# RingLight.net
KiCad netlist of a schematic drawn in EAGLE
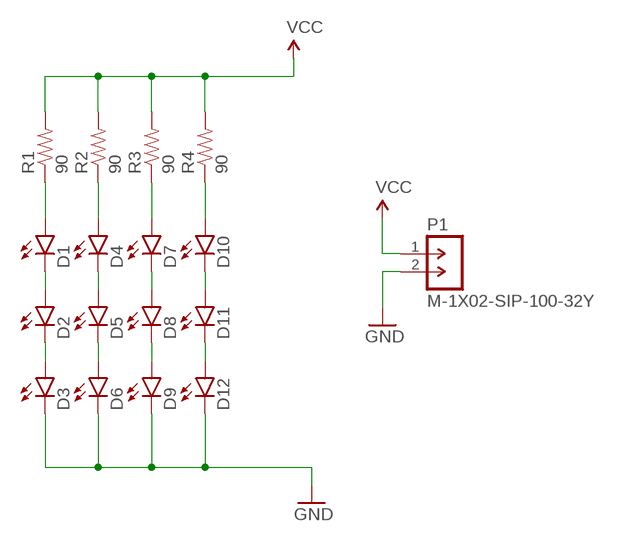
[diagram p0: schematic, sheet 1]

(export (version "E")
  (design (tool "Eeschema 10.0.6"))
  (components
    (comp (ref "D1")
      (value "LED1206")
      (footprint "eagle-import:LED-1206")
      (libsource (lib "eagle-import") (part "LED1206"))
    )
    (comp (ref "D2")
      (value "LED1206")
      (footprint "eagle-import:LED-1206")
      (libsource (lib "eagle-import") (part "LED1206"))
    )
    (comp (ref "D3")
      (value "LED1206")
      (footprint "eagle-import:LED-1206")
      (libsource (lib "eagle-import") (part "LED1206"))
    )
    (comp (ref "D4")
      (value "LED1206")
      (footprint "eagle-import:LED-1206")
      (libsource (lib "eagle-import") (part "LED1206"))
    )
    (comp (ref "D5")
      (value "LED1206")
      (footprint "eagle-import:LED-1206")
      (libsource (lib "eagle-import") (part "LED1206"))
    )
    (comp (ref "D6")
      (value "LED1206")
      (footprint "eagle-import:LED-1206")
      (libsource (lib "eagle-import") (part "LED1206"))
    )
    (comp (ref "D7")
      (value "LED1206")
      (footprint "eagle-import:LED-1206")
      (libsource (lib "eagle-import") (part "LED1206"))
    )
    (comp (ref "D8")
      (value "LED1206")
      (footprint "eagle-import:LED-1206")
      (libsource (lib "eagle-import") (part "LED1206"))
    )
    (comp (ref "D9")
      (value "LED1206")
      (footprint "eagle-import:LED-1206")
      (libsource (lib "eagle-import") (part "LED1206"))
    )
    (comp (ref "D10")
      (value "LED1206")
      (footprint "eagle-import:LED-1206")
      (libsource (lib "eagle-import") (part "LED1206"))
    )
    (comp (ref "D11")
      (value "LED1206")
      (footprint "eagle-import:LED-1206")
      (libsource (lib "eagle-import") (part "LED1206"))
    )
    (comp (ref "D12")
      (value "LED1206")
      (footprint "eagle-import:LED-1206")
      (libsource (lib "eagle-import") (part "LED1206"))
    )
    (comp (ref "P1")
      (value "M-1X02-SIP-100-32Y")
      (footprint "eagle-import:SIP-100-02-32Y")
      (libsource (lib "eagle-import") (part "M-1X02-SIP-100-32Y"))
    )
    (comp (ref "R1")
      (value "90")
      (footprint "eagle-import:1206")
      (libsource (lib "eagle-import") (part "RESISTOR1206"))
    )
    (comp (ref "R2")
      (value "90")
      (footprint "eagle-import:1206")
      (libsource (lib "eagle-import") (part "RESISTOR1206"))
    )
    (comp (ref "R3")
      (value "90")
      (footprint "eagle-import:1206")
      (libsource (lib "eagle-import") (part "RESISTOR1206"))
    )
    (comp (ref "R4")
      (value "90")
      (footprint "eagle-import:1206")
      (libsource (lib "eagle-import") (part "RESISTOR1206"))
    )
  )
  (nets
    (net (code "1") (name "GND") (class "Default")
      (node (ref "D12") (pin "C") (pinfunction "C_C") (pintype "passive"))
      (node (ref "D3") (pin "C") (pinfunction "C_C") (pintype "passive"))
      (node (ref "D6") (pin "C") (pinfunction "C_C") (pintype "passive"))
      (node (ref "D9") (pin "C") (pinfunction "C_C") (pintype "passive"))
      (node (ref "P1") (pin "2") (pinfunction "2_2") (pintype "passive"))
    )
    (net (code "2") (name "Net-(D1-PadA)") (class "Default")
      (node (ref "D1") (pin "A") (pinfunction "A_A") (pintype "passive"))
      (node (ref "R1") (pin "1") (pinfunction "1_1") (pintype "passive"))
    )
    (net (code "3") (name "Net-(D1-PadC)") (class "Default")
      (node (ref "D1") (pin "C") (pinfunction "C_C") (pintype "passive"))
      (node (ref "D2") (pin "A") (pinfunction "A_A") (pintype "passive"))
    )
    (net (code "4") (name "Net-(D2-PadC)") (class "Default")
      (node (ref "D2") (pin "C") (pinfunction "C_C") (pintype "passive"))
      (node (ref "D3") (pin "A") (pinfunction "A_A") (pintype "passive"))
    )
    (net (code "5") (name "Net-(D4-PadA)") (class "Default")
      (node (ref "D4") (pin "A") (pinfunction "A_A") (pintype "passive"))
      (node (ref "R2") (pin "1") (pinfunction "1_1") (pintype "passive"))
    )
    (net (code "6") (name "Net-(D4-PadC)") (class "Default")
      (node (ref "D4") (pin "C") (pinfunction "C_C") (pintype "passive"))
      (node (ref "D5") (pin "A") (pinfunction "A_A") (pintype "passive"))
    )
    (net (code "7") (name "Net-(D5-PadC)") (class "Default")
      (node (ref "D5") (pin "C") (pinfunction "C_C") (pintype "passive"))
      (node (ref "D6") (pin "A") (pinfunction "A_A") (pintype "passive"))
    )
    (net (code "8") (name "Net-(D7-PadA)") (class "Default")
      (node (ref "D7") (pin "A") (pinfunction "A_A") (pintype "passive"))
      (node (ref "R3") (pin "1") (pinfunction "1_1") (pintype "passive"))
    )
    (net (code "9") (name "Net-(D7-PadC)") (class "Default")
      (node (ref "D7") (pin "C") (pinfunction "C_C") (pintype "passive"))
      (node (ref "D8") (pin "A") (pinfunction "A_A") (pintype "passive"))
    )
    (net (code "10") (name "Net-(D8-PadC)") (class "Default")
      (node (ref "D8") (pin "C") (pinfunction "C_C") (pintype "passive"))
      (node (ref "D9") (pin "A") (pinfunction "A_A") (pintype "passive"))
    )
    (net (code "11") (name "Net-(D10-PadA)") (class "Default")
      (node (ref "D10") (pin "A") (pinfunction "A_A") (pintype "passive"))
      (node (ref "R4") (pin "1") (pinfunction "1_1") (pintype "passive"))
    )
    (net (code "12") (name "Net-(D10-PadC)") (class "Default")
      (node (ref "D10") (pin "C") (pinfunction "C_C") (pintype "passive"))
      (node (ref "D11") (pin "A") (pinfunction "A_A") (pintype "passive"))
    )
    (net (code "13") (name "Net-(D11-PadC)") (class "Default")
      (node (ref "D11") (pin "C") (pinfunction "C_C") (pintype "passive"))
      (node (ref "D12") (pin "A") (pinfunction "A_A") (pintype "passive"))
    )
    (net (code "14") (name "VCC") (class "Default")
      (node (ref "P1") (pin "1") (pinfunction "1_1") (pintype "passive"))
      (node (ref "R1") (pin "2") (pinfunction "2_2") (pintype "passive"))
      (node (ref "R2") (pin "2") (pinfunction "2_2") (pintype "passive"))
      (node (ref "R3") (pin "2") (pinfunction "2_2") (pintype "passive"))
      (node (ref "R4") (pin "2") (pinfunction "2_2") (pintype "passive"))
    )
  )
)
